# Power_Distribution.net
KiCad netlist of a schematic drawn in Altium Designer
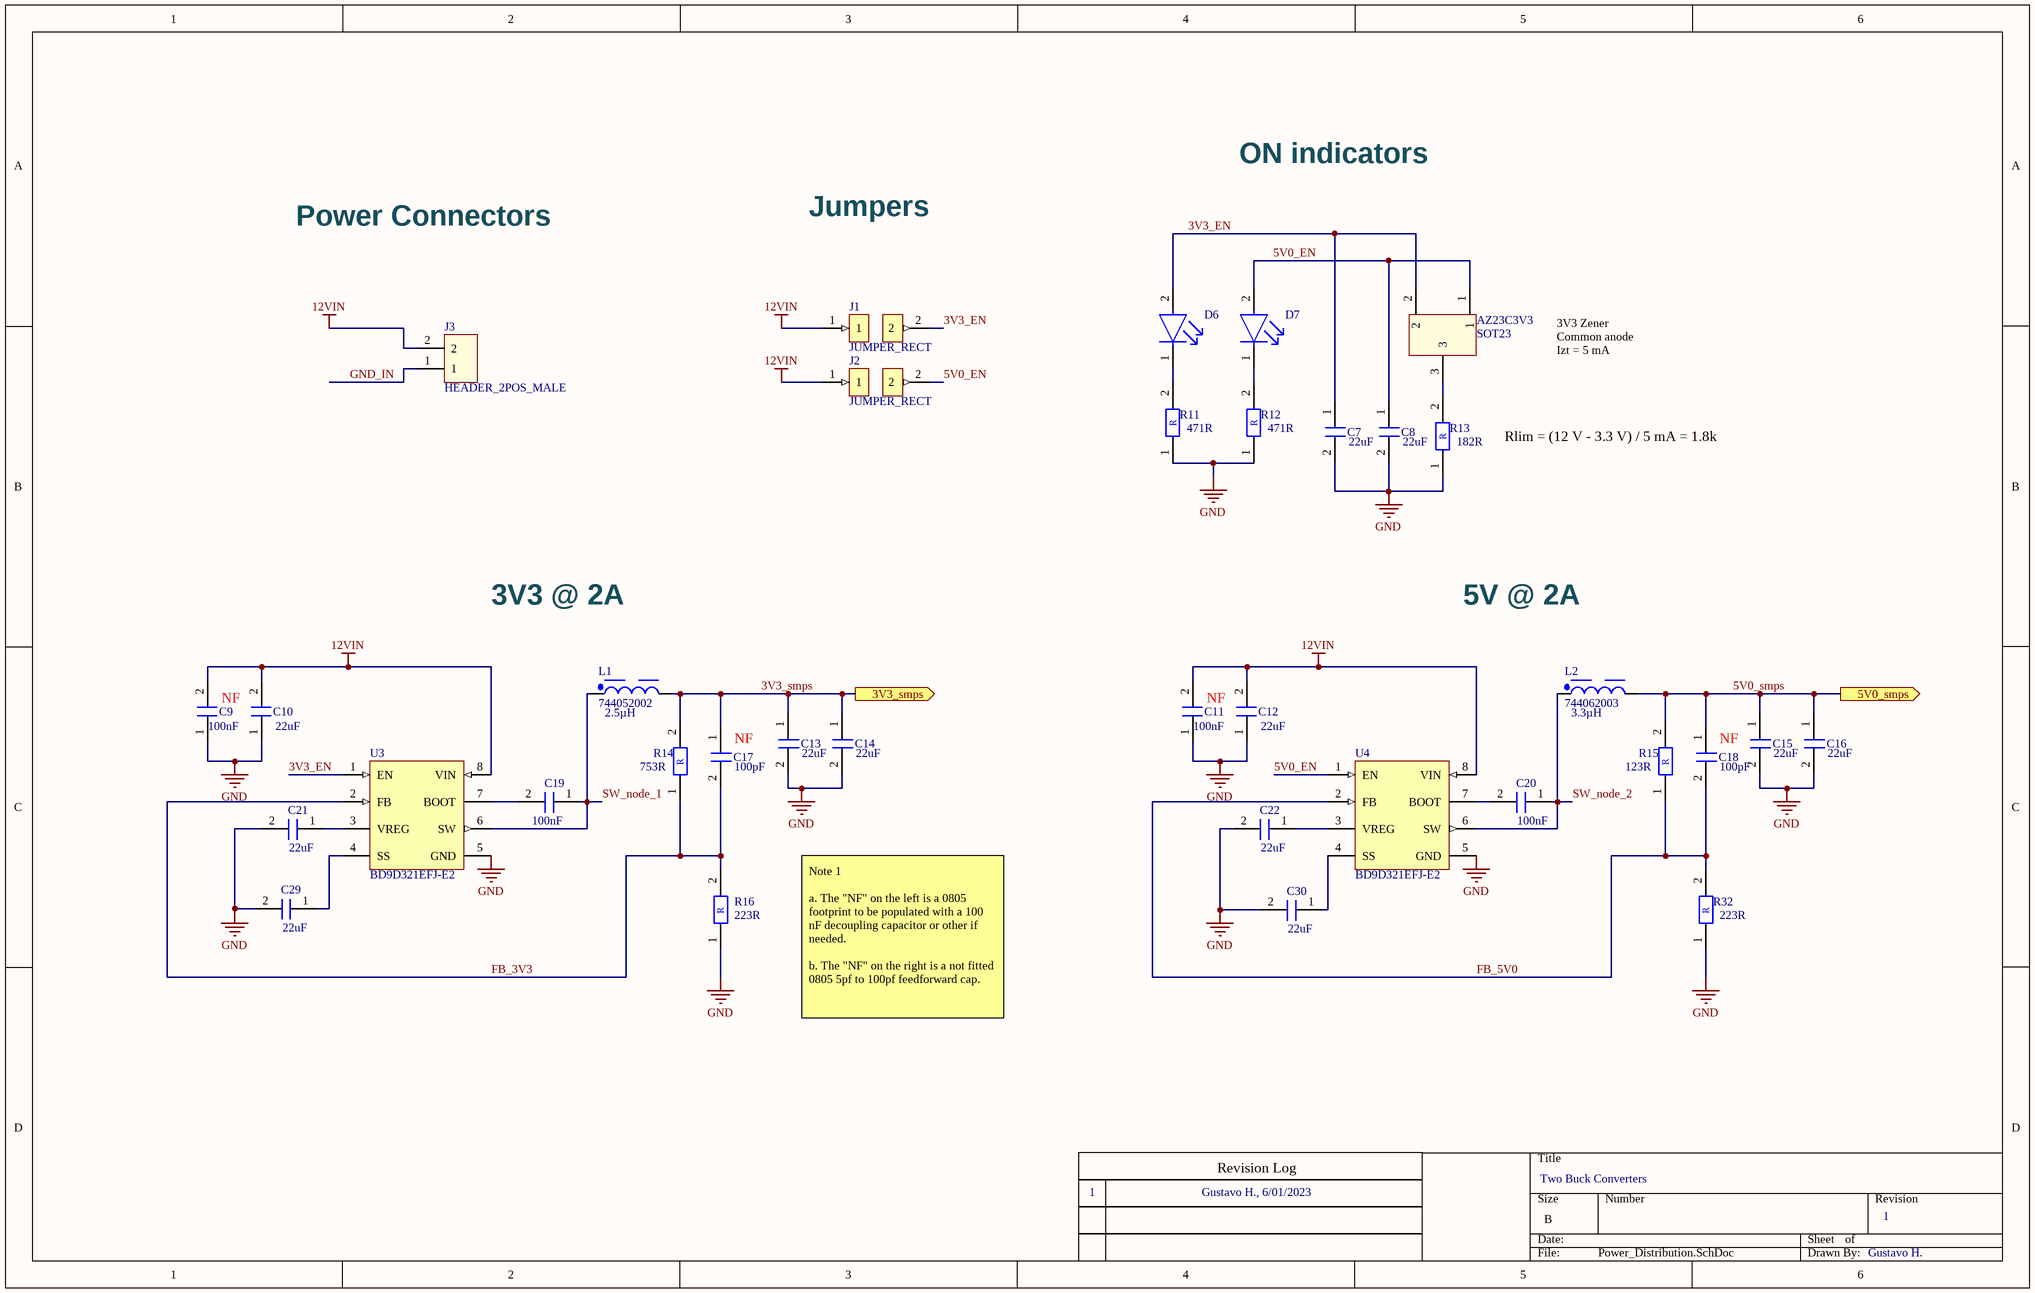
[diagram p0: Power_Distribution.SchDoc]

(export (version "E")
  (design (tool "Eeschema 10.0.6"))
  (components
    (comp (ref "AZ23C3V3")
      (value "SOT23")
      (footprint "SOT23")
      (libsource (lib "CREEA_starter_library") (part "SOT23"))
    )
    (comp (ref "C7")
      (value "P.N.")
      (footprint "0805_R")
      (description "Generic 0805 Capacitor")
      (fields (field (name "CAPACITANCE") "22uF"))
      (libsource (lib "CREEA_starter_library") (part "0805_C"))
    )
    (comp (ref "C8")
      (value "P.N.")
      (footprint "0805_R")
      (description "Generic 0805 Capacitor")
      (fields (field (name "CAPACITANCE") "22uF"))
      (libsource (lib "CREEA_starter_library") (part "0805_C"))
    )
    (comp (ref "C9")
      (value "P.N.")
      (footprint "0805_R")
      (description "Generic 0805 Capacitor")
      (fields (field (name "CAPACITANCE") "100nF"))
      (libsource (lib "CREEA_starter_library") (part "0805_C"))
    )
    (comp (ref "C10")
      (value "P.N.")
      (footprint "0805_R")
      (description "Generic 0805 Capacitor")
      (fields (field (name "CAPACITANCE") "22uF"))
      (libsource (lib "CREEA_starter_library") (part "0805_C"))
    )
    (comp (ref "C11")
      (value "P.N.")
      (footprint "0805_R")
      (description "Generic 0805 Capacitor")
      (fields (field (name "CAPACITANCE") "100nF"))
      (libsource (lib "CREEA_starter_library") (part "0805_C"))
    )
    (comp (ref "C12")
      (value "P.N.")
      (footprint "0805_R")
      (description "Generic 0805 Capacitor")
      (fields (field (name "CAPACITANCE") "22uF"))
      (libsource (lib "CREEA_starter_library") (part "0805_C"))
    )
    (comp (ref "C13")
      (value "P.N.")
      (footprint "0805_R")
      (description "Generic 0805 Capacitor")
      (fields (field (name "CAPACITANCE") "22uF"))
      (libsource (lib "CREEA_starter_library") (part "0805_C"))
    )
    (comp (ref "C14")
      (value "P.N.")
      (footprint "0805_R")
      (description "Generic 0805 Capacitor")
      (fields (field (name "CAPACITANCE") "22uF"))
      (libsource (lib "CREEA_starter_library") (part "0805_C"))
    )
    (comp (ref "C15")
      (value "P.N.")
      (footprint "0805_R")
      (description "Generic 0805 Capacitor")
      (fields (field (name "CAPACITANCE") "22uF"))
      (libsource (lib "CREEA_starter_library") (part "0805_C"))
    )
    (comp (ref "C16")
      (value "P.N.")
      (footprint "0805_R")
      (description "Generic 0805 Capacitor")
      (fields (field (name "CAPACITANCE") "22uF"))
      (libsource (lib "CREEA_starter_library") (part "0805_C"))
    )
    (comp (ref "C17")
      (value "P.N.")
      (footprint "0805_R")
      (description "Generic 0805 Capacitor")
      (fields (field (name "CAPACITANCE") "100pF"))
      (libsource (lib "CREEA_starter_library") (part "0805_C"))
    )
    (comp (ref "C18")
      (value "P.N.")
      (footprint "0805_R")
      (description "Generic 0805 Capacitor")
      (fields (field (name "CAPACITANCE") "100pF"))
      (libsource (lib "CREEA_starter_library") (part "0805_C"))
    )
    (comp (ref "C19")
      (value "P.N.")
      (footprint "0805_R")
      (description "Generic 0805 Capacitor")
      (fields (field (name "CAPACITANCE") "100nF"))
      (libsource (lib "CREEA_starter_library") (part "0805_C"))
    )
    (comp (ref "C20")
      (value "P.N.")
      (footprint "0805_R")
      (description "Generic 0805 Capacitor")
      (fields (field (name "CAPACITANCE") "100nF"))
      (libsource (lib "CREEA_starter_library") (part "0805_C"))
    )
    (comp (ref "C21")
      (value "P.N.")
      (footprint "0805_R")
      (description "Generic 0805 Capacitor")
      (fields (field (name "CAPACITANCE") "22uF"))
      (libsource (lib "CREEA_starter_library") (part "0805_C"))
    )
    (comp (ref "C22")
      (value "P.N.")
      (footprint "0805_R")
      (description "Generic 0805 Capacitor")
      (fields (field (name "CAPACITANCE") "22uF"))
      (libsource (lib "CREEA_starter_library") (part "0805_C"))
    )
    (comp (ref "C29")
      (value "P.N.")
      (footprint "0805_R")
      (description "Generic 0805 Capacitor")
      (fields (field (name "CAPACITANCE") "22uF"))
      (libsource (lib "CREEA_starter_library") (part "0805_C"))
    )
    (comp (ref "C30")
      (value "P.N.")
      (footprint "0805_R")
      (description "Generic 0805 Capacitor")
      (fields (field (name "CAPACITANCE") "22uF"))
      (libsource (lib "CREEA_starter_library") (part "0805_C"))
    )
    (comp (ref "D6")
      (value "LTST-C191TBKT")
      (footprint "FP-LTST-C191TBKT-MFG")
      (description "LED BLUE CLEAR CHIP SMD")
      (libsource (lib "Altium Content Vault") (part "8706943c75ba83719d021d2fdc84c58"))
    )
    (comp (ref "D7")
      (value "LTST-C191TBKT")
      (footprint "FP-LTST-C191TBKT-MFG")
      (description "LED BLUE CLEAR CHIP SMD")
      (libsource (lib "Altium Content Vault") (part "8706943c75ba83719d021d2fdc84c58"))
    )
    (comp (ref "J1")
      (value "JUMPER_RECT")
      (footprint "JUMPER_RECT")
      (description "Small rectangular jumper")
      (libsource (lib "CREEA_starter_library") (part "JUMPER_RECT"))
    )
    (comp (ref "J2")
      (value "JUMPER_RECT")
      (footprint "JUMPER_RECT")
      (description "Small rectangular jumper")
      (libsource (lib "CREEA_starter_library") (part "JUMPER_RECT"))
    )
    (comp (ref "J3")
      (value "HEADER_2POS_MALE")
      (footprint "HEADER_2POS_MALE_VERT_2.54MM")
      (libsource (lib "CREEA_starter_library") (part "HEADER_2POS_MALE"))
    )
    (comp (ref "L1")
      (value "744052002")
      (footprint "WE-TPC_5818")
      (fields (field (name "INDUCTANCE") "2.5µH"))
      (libsource (lib "Altium Content Vault") (part "Inductor - 2"))
    )
    (comp (ref "L2")
      (value "744062003")
      (footprint "WE-TPC_6823")
      (fields (field (name "TOLERANCE") "30%") (field (name "INDUCTANCE") "3.3µH"))
      (libsource (lib "Altium Content Vault") (part "Inductor - 2"))
    )
    (comp (ref "R11")
      (value "P.N.")
      (footprint "0805_R")
      (description "Generic 0805 Resistor")
      (fields (field (name "RESISTANCE") "471R"))
      (libsource (lib "CREEA_starter_library") (part "0805_R"))
    )
    (comp (ref "R12")
      (value "P.N.")
      (footprint "0805_R")
      (description "Generic 0805 Resistor")
      (fields (field (name "RESISTANCE") "471R"))
      (libsource (lib "CREEA_starter_library") (part "0805_R"))
    )
    (comp (ref "R13")
      (value "P.N.")
      (footprint "0805_R")
      (description "Generic 0805 Resistor")
      (fields (field (name "RESISTANCE") "182R"))
      (libsource (lib "CREEA_starter_library") (part "0805_R"))
    )
    (comp (ref "R14")
      (value "P.N.")
      (footprint "0805_R")
      (description "Generic 0805 Resistor")
      (fields (field (name "RESISTANCE") "753R"))
      (libsource (lib "CREEA_starter_library") (part "0805_R"))
    )
    (comp (ref "R15")
      (value "P.N.")
      (footprint "0805_R")
      (description "Generic 0805 Resistor")
      (fields (field (name "RESISTANCE") "123R"))
      (libsource (lib "CREEA_starter_library") (part "0805_R"))
    )
    (comp (ref "R16")
      (value "P.N.")
      (footprint "0805_R")
      (description "Generic 0805 Resistor")
      (fields (field (name "RESISTANCE") "223R"))
      (libsource (lib "CREEA_starter_library") (part "0805_R"))
    )
    (comp (ref "R32")
      (value "P.N.")
      (footprint "0805_R")
      (description "Generic 0805 Resistor")
      (fields (field (name "RESISTANCE") "223R"))
      (libsource (lib "CREEA_starter_library") (part "0805_R"))
    )
    (comp (ref "U3")
      (value "BD9D321EFJ-E2")
      (footprint "SOIC127P600X100-8N")
      (description "ICREGBUCKADJ3ASYNC8HTSOP")
      (libsource (lib "Cetys University") (part "BD9D321EFJ-E2-Symbol-1"))
    )
    (comp (ref "U4")
      (value "BD9D321EFJ-E2")
      (footprint "SOIC127P600X100-8N")
      (description "ICREGBUCKADJ3ASYNC8HTSOP")
      (libsource (lib "Cetys University") (part "BD9D321EFJ-E2-Symbol-1"))
    )
  )
  (nets
    (net (code "1") (name "/3V3_EN") (class "Default")
      (node (ref "AZ23C3V3") (pin "2") (pinfunction "2_2") (pintype "passive"))
      (node (ref "C7") (pin "1") (pinfunction "1_1") (pintype "passive"))
      (node (ref "D6") (pin "2") (pinfunction "A_2") (pintype "passive"))
      (node (ref "J1") (pin "2") (pinfunction "2_2") (pintype "output"))
      (node (ref "U3") (pin "1") (pinfunction "EN_1") (pintype "input"))
    )
    (net (code "2") (name "/3V3_smps") (class "Default")
      (node (ref "C13") (pin "1") (pinfunction "1_1") (pintype "passive"))
      (node (ref "C14") (pin "1") (pinfunction "1_1") (pintype "passive"))
      (node (ref "C17") (pin "1") (pinfunction "1_1") (pintype "passive"))
      (node (ref "L1") (pin "2") (pinfunction "2_2") (pintype "passive"))
      (node (ref "R14") (pin "2") (pinfunction "2_2") (pintype "passive"))
    )
    (net (code "3") (name "/5V0_EN") (class "Default")
      (node (ref "AZ23C3V3") (pin "1") (pinfunction "1_1") (pintype "passive"))
      (node (ref "C8") (pin "1") (pinfunction "1_1") (pintype "passive"))
      (node (ref "D7") (pin "2") (pinfunction "A_2") (pintype "passive"))
      (node (ref "J2") (pin "2") (pinfunction "2_2") (pintype "output"))
      (node (ref "U4") (pin "1") (pinfunction "EN_1") (pintype "input"))
    )
    (net (code "4") (name "/5V0_smps") (class "Default")
      (node (ref "C15") (pin "1") (pinfunction "1_1") (pintype "passive"))
      (node (ref "C16") (pin "1") (pinfunction "1_1") (pintype "passive"))
      (node (ref "C18") (pin "1") (pinfunction "1_1") (pintype "passive"))
      (node (ref "L2") (pin "2") (pinfunction "2_2") (pintype "passive"))
      (node (ref "R15") (pin "2") (pinfunction "2_2") (pintype "passive"))
    )
    (net (code "5") (name "/FB_3V3") (class "Default")
      (node (ref "C17") (pin "2") (pinfunction "2_2") (pintype "passive"))
      (node (ref "R14") (pin "1") (pinfunction "1_1") (pintype "passive"))
      (node (ref "R16") (pin "2") (pinfunction "2_2") (pintype "passive"))
      (node (ref "U3") (pin "2") (pinfunction "FB_2") (pintype "input"))
    )
    (net (code "6") (name "/FB_5V0") (class "Default")
      (node (ref "C18") (pin "2") (pinfunction "2_2") (pintype "passive"))
      (node (ref "R15") (pin "1") (pinfunction "1_1") (pintype "passive"))
      (node (ref "R32") (pin "2") (pinfunction "2_2") (pintype "passive"))
      (node (ref "U4") (pin "2") (pinfunction "FB_2") (pintype "input"))
    )
    (net (code "7") (name "/GND_IN") (class "Default")
      (node (ref "J3") (pin "1") (pinfunction "1_1") (pintype "passive"))
    )
    (net (code "8") (name "/SW_node_1") (class "Default")
      (node (ref "C19") (pin "1") (pinfunction "1_1") (pintype "passive"))
      (node (ref "L1") (pin "1") (pinfunction "1_1") (pintype "passive"))
      (node (ref "U3") (pin "6") (pinfunction "SW_6") (pintype "output"))
    )
    (net (code "9") (name "/SW_node_2") (class "Default")
      (node (ref "C20") (pin "1") (pinfunction "1_1") (pintype "passive"))
      (node (ref "L2") (pin "1") (pinfunction "1_1") (pintype "passive"))
      (node (ref "U4") (pin "6") (pinfunction "SW_6") (pintype "output"))
    )
    (net (code "10") (name "12VIN") (class "Default")
      (node (ref "C10") (pin "2") (pinfunction "2_2") (pintype "passive"))
      (node (ref "C11") (pin "2") (pinfunction "2_2") (pintype "passive"))
      (node (ref "C12") (pin "2") (pinfunction "2_2") (pintype "passive"))
      (node (ref "C9") (pin "2") (pinfunction "2_2") (pintype "passive"))
      (node (ref "J1") (pin "1") (pinfunction "1_1") (pintype "input"))
      (node (ref "J2") (pin "1") (pinfunction "1_1") (pintype "input"))
      (node (ref "J3") (pin "2") (pinfunction "2_2") (pintype "passive"))
      (node (ref "U3") (pin "8") (pinfunction "VIN_8") (pintype "input"))
      (node (ref "U4") (pin "8") (pinfunction "VIN_8") (pintype "input"))
    )
    (net (code "11") (name "GND") (class "Default")
      (node (ref "C10") (pin "1") (pinfunction "1_1") (pintype "passive"))
      (node (ref "C11") (pin "1") (pinfunction "1_1") (pintype "passive"))
      (node (ref "C12") (pin "1") (pinfunction "1_1") (pintype "passive"))
      (node (ref "C13") (pin "2") (pinfunction "2_2") (pintype "passive"))
      (node (ref "C14") (pin "2") (pinfunction "2_2") (pintype "passive"))
      (node (ref "C15") (pin "2") (pinfunction "2_2") (pintype "passive"))
      (node (ref "C16") (pin "2") (pinfunction "2_2") (pintype "passive"))
      (node (ref "C21") (pin "2") (pinfunction "2_2") (pintype "passive"))
      (node (ref "C22") (pin "2") (pinfunction "2_2") (pintype "passive"))
      (node (ref "C29") (pin "2") (pinfunction "2_2") (pintype "passive"))
      (node (ref "C30") (pin "2") (pinfunction "2_2") (pintype "passive"))
      (node (ref "C7") (pin "2") (pinfunction "2_2") (pintype "passive"))
      (node (ref "C8") (pin "2") (pinfunction "2_2") (pintype "passive"))
      (node (ref "C9") (pin "1") (pinfunction "1_1") (pintype "passive"))
      (node (ref "R11") (pin "1") (pinfunction "1_1") (pintype "passive"))
      (node (ref "R12") (pin "1") (pinfunction "1_1") (pintype "passive"))
      (node (ref "R13") (pin "1") (pinfunction "1_1") (pintype "passive"))
      (node (ref "R16") (pin "1") (pinfunction "1_1") (pintype "passive"))
      (node (ref "R32") (pin "1") (pinfunction "1_1") (pintype "passive"))
      (node (ref "U3") (pin "5") (pinfunction "GND_5") (pintype "passive"))
      (node (ref "U4") (pin "5") (pinfunction "GND_5") (pintype "passive"))
    )
    (net (code "12") (name "Net-(AZ23C3V3-Pad3)") (class "Default")
      (node (ref "AZ23C3V3") (pin "3") (pinfunction "3_3") (pintype "passive"))
      (node (ref "R13") (pin "2") (pinfunction "2_2") (pintype "passive"))
    )
    (net (code "13") (name "Net-(D6-C)") (class "Default")
      (node (ref "D6") (pin "1") (pinfunction "C_1") (pintype "passive"))
      (node (ref "R11") (pin "2") (pinfunction "2_2") (pintype "passive"))
    )
    (net (code "14") (name "Net-(D7-C)") (class "Default")
      (node (ref "D7") (pin "1") (pinfunction "C_1") (pintype "passive"))
      (node (ref "R12") (pin "2") (pinfunction "2_2") (pintype "passive"))
    )
    (net (code "15") (name "Net-(U3-BOOT)") (class "Default")
      (node (ref "C19") (pin "2") (pinfunction "2_2") (pintype "passive"))
      (node (ref "U3") (pin "7") (pinfunction "BOOT_7") (pintype "passive"))
    )
    (net (code "16") (name "Net-(U3-SS)") (class "Default")
      (node (ref "C29") (pin "1") (pinfunction "1_1") (pintype "passive"))
      (node (ref "U3") (pin "4") (pinfunction "SS_4") (pintype "passive"))
    )
    (net (code "17") (name "Net-(U3-VREG)") (class "Default")
      (node (ref "C21") (pin "1") (pinfunction "1_1") (pintype "passive"))
      (node (ref "U3") (pin "3") (pinfunction "VREG_3") (pintype "passive"))
    )
    (net (code "18") (name "Net-(U4-BOOT)") (class "Default")
      (node (ref "C20") (pin "2") (pinfunction "2_2") (pintype "passive"))
      (node (ref "U4") (pin "7") (pinfunction "BOOT_7") (pintype "passive"))
    )
    (net (code "19") (name "Net-(U4-SS)") (class "Default")
      (node (ref "C30") (pin "1") (pinfunction "1_1") (pintype "passive"))
      (node (ref "U4") (pin "4") (pinfunction "SS_4") (pintype "passive"))
    )
    (net (code "20") (name "Net-(U4-VREG)") (class "Default")
      (node (ref "C22") (pin "1") (pinfunction "1_1") (pintype "passive"))
      (node (ref "U4") (pin "3") (pinfunction "VREG_3") (pintype "passive"))
    )
  )
)
